# Plata1.net
KiCad netlist of a schematic drawn in EAGLE
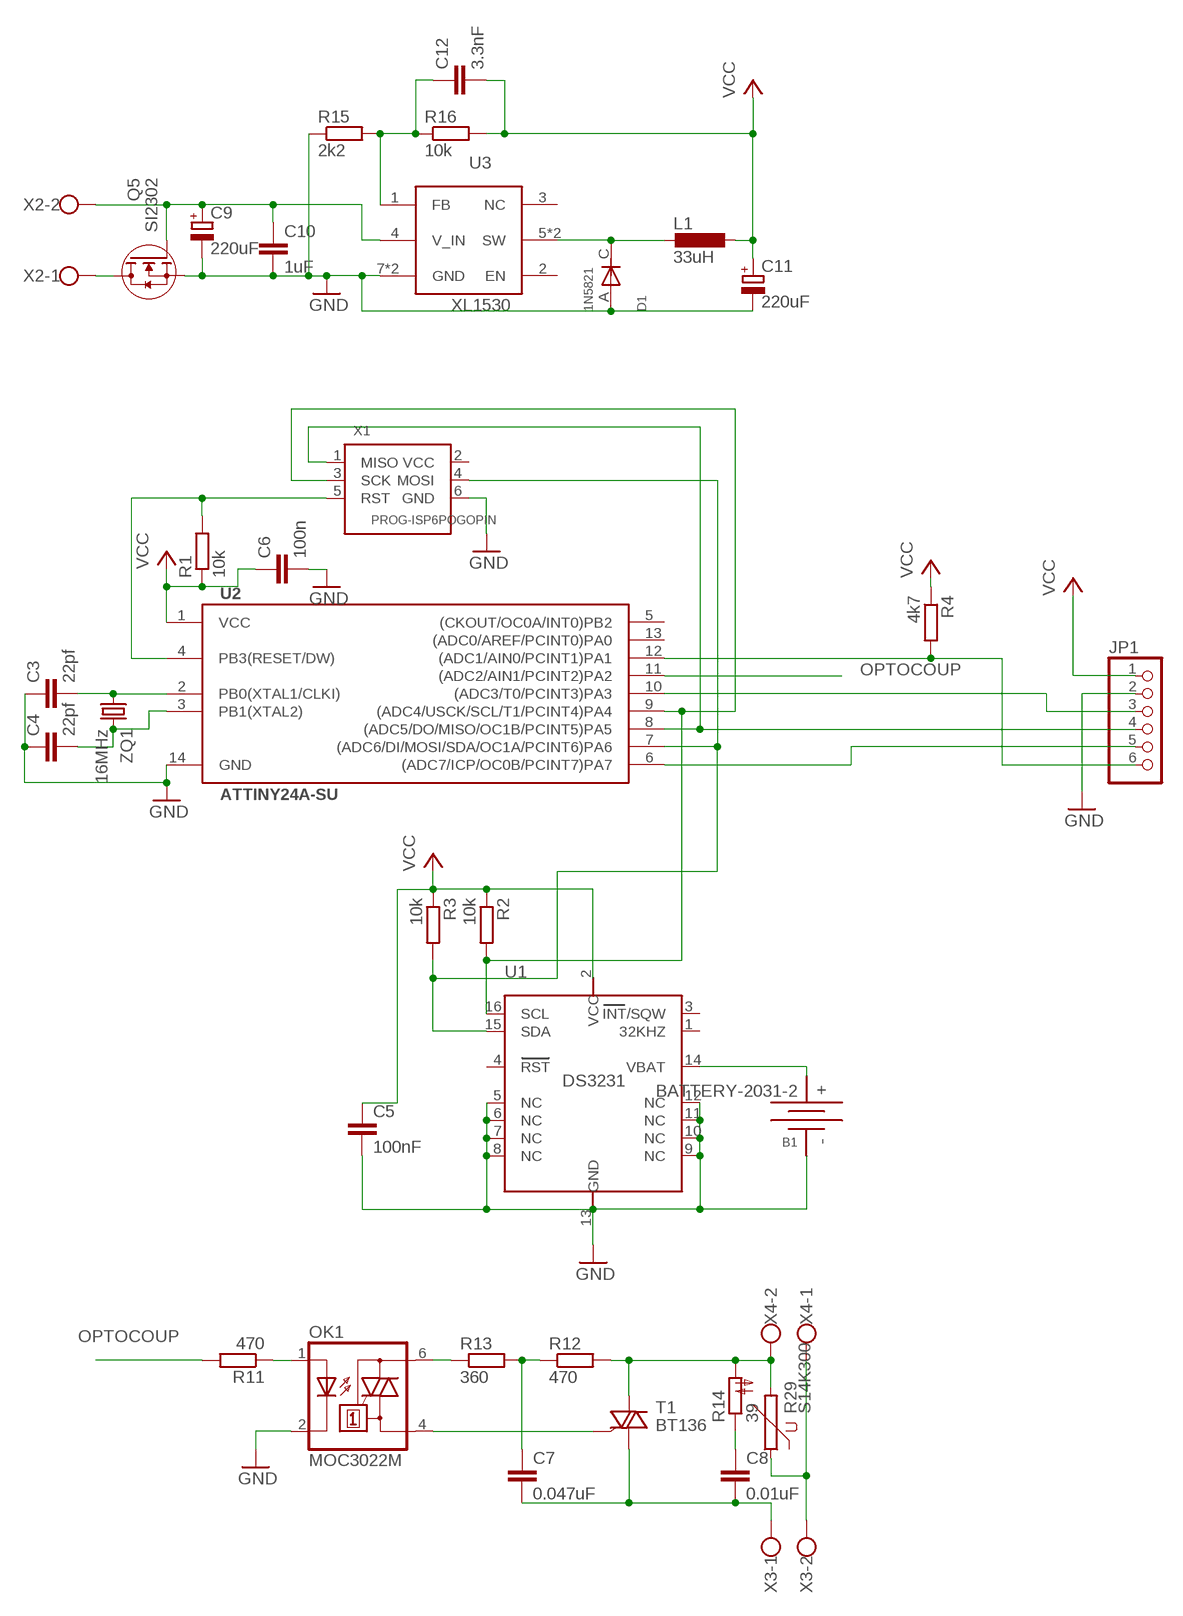
[diagram p0: schematic, sheet 1]

(export (version "E")
  (design (tool "Eeschema 10.0.6"))
  (components
    (comp (ref "B1")
      (value "BATTERY-2031-2")
      (footprint "eagle-import:BTH2032-2")
      (libsource (lib "eagle-import") (part "BATTERY-2031-2"))
    )
    (comp (ref "C3")
      (value "22pf")
      (footprint "eagle-import:C0603")
      (libsource (lib "eagle-import") (part "C-EUC0603"))
    )
    (comp (ref "C4")
      (value "22pf")
      (footprint "eagle-import:C0603")
      (libsource (lib "eagle-import") (part "C-EUC0603"))
    )
    (comp (ref "C5")
      (value "100nF")
      (footprint "eagle-import:C0603")
      (libsource (lib "eagle-import") (part "C-EUC0603"))
    )
    (comp (ref "C6")
      (value "100n")
      (footprint "eagle-import:C0603")
      (libsource (lib "eagle-import") (part "C-EUC0603"))
    )
    (comp (ref "C7")
      (value "0.047uF")
      (footprint "eagle-import:C150-054X183")
      (libsource (lib "eagle-import") (part "C-EU150-054X183"))
    )
    (comp (ref "C8")
      (value "0.01uF")
      (footprint "eagle-import:C102-043X133")
      (libsource (lib "eagle-import") (part "C-EU102-043X133"))
    )
    (comp (ref "C9")
      (value "220uF")
      (footprint "eagle-import:E2,5-6E")
      (libsource (lib "eagle-import") (part "CPOL-EUE2,5-6E"))
    )
    (comp (ref "C10")
      (value "1uF")
      (footprint "eagle-import:C0805")
      (libsource (lib "eagle-import") (part "C-EUC0805"))
    )
    (comp (ref "C11")
      (value "220uF")
      (footprint "eagle-import:E2,5-6E")
      (libsource (lib "eagle-import") (part "CPOL-EUE2,5-6E"))
    )
    (comp (ref "C12")
      (value "3.3nF")
      (footprint "eagle-import:C0805")
      (libsource (lib "eagle-import") (part "C-EUC0805"))
    )
    (comp (ref "D1")
      (value "1N5821")
      (footprint "eagle-import:DO214AC")
      (libsource (lib "eagle-import") (part "DIODESMD"))
    )
    (comp (ref "JP1")
      (value "PINHD-1X6")
      (footprint "eagle-import:1X06")
      (libsource (lib "eagle-import") (part "PINHD-1X6"))
    )
    (comp (ref "L1")
      (value "33uH")
      (footprint "eagle-import:L-SMD-D10")
      (libsource (lib "eagle-import") (part "L-SMD"))
    )
    (comp (ref "OK1")
      (value "MOC3022M")
      (footprint "eagle-import:DIL06")
      (fields (field (name "MF") "FAIRCHILD SEMICONDUCTOR") (field (name "MPN") "MOC3022-M"))
      (libsource (lib "eagle-import") (part "MOC30M22"))
    )
    (comp (ref "Q5")
      (value "SI2302")
      (footprint "eagle-import:SOT-23-GSD")
      (libsource (lib "eagle-import") (part "SI2302"))
    )
    (comp (ref "R1")
      (value "10k")
      (footprint "eagle-import:R0805")
      (libsource (lib "eagle-import") (part "R-EU_R0805"))
    )
    (comp (ref "R2")
      (value "10k")
      (footprint "eagle-import:R0805")
      (libsource (lib "eagle-import") (part "R-EU_R0805"))
    )
    (comp (ref "R3")
      (value "10k")
      (footprint "eagle-import:R0805")
      (libsource (lib "eagle-import") (part "R-EU_R0805"))
    )
    (comp (ref "R4")
      (value "4k7")
      (footprint "eagle-import:R0805")
      (libsource (lib "eagle-import") (part "R-EU_R0805"))
    )
    (comp (ref "R11")
      (value "470")
      (footprint "eagle-import:R0805")
      (libsource (lib "eagle-import") (part "R-EU_R0805"))
    )
    (comp (ref "R12")
      (value "470")
      (footprint "eagle-import:0207_7")
      (libsource (lib "eagle-import") (part "R-EU_0207/7"))
    )
    (comp (ref "R13")
      (value "360")
      (footprint "eagle-import:0207_7")
      (libsource (lib "eagle-import") (part "R-EU_0207/7"))
    )
    (comp (ref "R14")
      (value "39")
      (footprint "eagle-import:0207_7")
      (libsource (lib "eagle-import") (part "R-EU_0207/7"))
    )
    (comp (ref "R15")
      (value "2k2")
      (footprint "eagle-import:R0603")
      (libsource (lib "eagle-import") (part "R-EU_R0603"))
    )
    (comp (ref "R16")
      (value "10k")
      (footprint "eagle-import:R0603")
      (libsource (lib "eagle-import") (part "R-EU_R0603"))
    )
    (comp (ref "R29")
      (value "S14K300")
      (footprint "eagle-import:S14K300")
      (libsource (lib "eagle-import") (part "S14K300"))
    )
    (comp (ref "T1")
      (value "BT136")
      (footprint "eagle-import:TO220AB")
      (libsource (lib "eagle-import") (part "BT136"))
    )
    (comp (ref "U1")
      (value "DS3231")
      (footprint "eagle-import:SO16L")
      (libsource (lib "eagle-import") (part "DS3231"))
    )
    (comp (ref "U2")
      (value "ATTINY24A-SU")
      (footprint "eagle-import:SO14")
      (libsource (lib "eagle-import") (part "ATTINY24A-SU"))
    )
    (comp (ref "U3")
      (value "XL1530")
      (footprint "eagle-import:SOP08")
      (libsource (lib "eagle-import") (part "XL1530"))
    )
    (comp (ref "X1")
      (value "PROG-ISP6POGOPIN")
      (footprint "eagle-import:PROG_POGOPIN")
      (libsource (lib "eagle-import") (part "PROG-ISP6POGOPIN"))
    )
    (comp (ref "X2")
      (value "W237-102")
      (footprint "eagle-import:W237-102")
      (fields (field (name "MPN") "237-102"))
      (libsource (lib "eagle-import") (part "W237-102"))
    )
    (comp (ref "X3")
      (value "W237-102")
      (footprint "eagle-import:W237-102")
      (fields (field (name "MPN") "237-102"))
      (libsource (lib "eagle-import") (part "W237-102"))
    )
    (comp (ref "X4")
      (value "W237-102")
      (footprint "eagle-import:W237-102")
      (fields (field (name "MPN") "237-102"))
      (libsource (lib "eagle-import") (part "W237-102"))
    )
    (comp (ref "ZQ1")
      (value "16MHz")
      (footprint "eagle-import:HC49_S")
      (libsource (lib "eagle-import") (part "CRYSTALHC49S"))
    )
  )
  (nets
    (net (code "1") (name "/OPTOCOUP") (class "Default")
      (node (ref "R11") (pin "2") (pinfunction "2_2") (pintype "passive"))
      (node (ref "U2") (pin "11") (pinfunction "(ADC2/AIN1/PCINT2)PA2_11") (pintype "bidirectional"))
    )
    (net (code "2") (name "GND") (class "Default")
      (node (ref "B1") (pin "-") (pinfunction "-_-") (pintype "power_in"))
      (node (ref "C10") (pin "2") (pinfunction "2_2") (pintype "passive"))
      (node (ref "C11") (pin "-") (pinfunction "-_-") (pintype "passive"))
      (node (ref "C3") (pin "1") (pinfunction "1_1") (pintype "passive"))
      (node (ref "C4") (pin "1") (pinfunction "1_1") (pintype "passive"))
      (node (ref "C5") (pin "2") (pinfunction "2_2") (pintype "passive"))
      (node (ref "C6") (pin "2") (pinfunction "2_2") (pintype "passive"))
      (node (ref "C9") (pin "-") (pinfunction "-_-") (pintype "passive"))
      (node (ref "D1") (pin "A") (pinfunction "ANOD_A") (pintype "power_in"))
      (node (ref "JP1") (pin "2") (pinfunction "2_2") (pintype "passive"))
      (node (ref "OK1") (pin "2") (pinfunction "C_2") (pintype "passive"))
      (node (ref "Q5") (pin "S") (pinfunction "S_S") (pintype "passive"))
      (node (ref "R15") (pin "1") (pinfunction "1_1") (pintype "passive"))
      (node (ref "U1") (pin "10") (pinfunction "NC_10") (pintype "bidirectional"))
      (node (ref "U1") (pin "11") (pinfunction "NC_11") (pintype "bidirectional"))
      (node (ref "U1") (pin "12") (pinfunction "NC_12") (pintype "bidirectional"))
      (node (ref "U1") (pin "13") (pinfunction "GND_13") (pintype "power_in"))
      (node (ref "U1") (pin "5") (pinfunction "NC_5") (pintype "bidirectional"))
      (node (ref "U1") (pin "6") (pinfunction "NC_6") (pintype "bidirectional"))
      (node (ref "U1") (pin "7") (pinfunction "NC_7") (pintype "bidirectional"))
      (node (ref "U1") (pin "8") (pinfunction "NC_8") (pintype "bidirectional"))
      (node (ref "U1") (pin "9") (pinfunction "NC_9") (pintype "bidirectional"))
      (node (ref "U2") (pin "14") (pinfunction "GND_14") (pintype "power_in"))
      (node (ref "U3") (pin "7") (pinfunction "GND_7") (pintype "bidirectional"))
      (node (ref "U3") (pin "8") (pinfunction "GND_8") (pintype "bidirectional"))
      (node (ref "X1") (pin "6") (pinfunction "GND_6") (pintype "power_in"))
    )
    (net (code "3") (name "Net-(C7-Pad1)") (class "Default")
      (node (ref "C7") (pin "1") (pinfunction "1_1") (pintype "passive"))
      (node (ref "R12") (pin "1") (pinfunction "1_1") (pintype "passive"))
      (node (ref "R13") (pin "2") (pinfunction "2_2") (pintype "passive"))
    )
    (net (code "4") (name "Net-(C8-Pad1)") (class "Default")
      (node (ref "C8") (pin "1") (pinfunction "1_1") (pintype "passive"))
      (node (ref "R14") (pin "1") (pinfunction "1_1") (pintype "passive"))
    )
    (net (code "5") (name "Net-(D1-KATOD)") (class "Default")
      (node (ref "D1") (pin "C") (pinfunction "KATOD_C") (pintype "power_in"))
      (node (ref "L1") (pin "P$2") (pinfunction "2_P$2") (pintype "passive"))
      (node (ref "U3") (pin "5") (pinfunction "SW_5") (pintype "bidirectional"))
      (node (ref "U3") (pin "6") (pinfunction "SW_6") (pintype "bidirectional"))
    )
    (net (code "6") (name "Net-(OK1-A)") (class "Default")
      (node (ref "OK1") (pin "1") (pinfunction "A_1") (pintype "passive"))
      (node (ref "R11") (pin "1") (pinfunction "1_1") (pintype "passive"))
    )
    (net (code "7") (name "Net-(OK1-A1)") (class "Default")
      (node (ref "OK1") (pin "4") (pinfunction "A1_4") (pintype "passive"))
      (node (ref "T1") (pin "3") (pinfunction "G_3") (pintype "passive"))
    )
    (net (code "8") (name "Net-(OK1-A2)") (class "Default")
      (node (ref "OK1") (pin "6") (pinfunction "A2_6") (pintype "passive"))
      (node (ref "R13") (pin "1") (pinfunction "1_1") (pintype "passive"))
    )
    (net (code "9") (name "Net-(T1-A1)") (class "Default")
      (node (ref "C7") (pin "2") (pinfunction "2_2") (pintype "passive"))
      (node (ref "C8") (pin "2") (pinfunction "2_2") (pintype "passive"))
      (node (ref "T1") (pin "1") (pinfunction "A1_1") (pintype "passive"))
      (node (ref "X3") (pin "1") (pinfunction "KL_1") (pintype "passive"))
    )
    (net (code "10") (name "Net-(T1-A2)") (class "Default")
      (node (ref "R12") (pin "2") (pinfunction "2_2") (pintype "passive"))
      (node (ref "R14") (pin "2") (pinfunction "2_2") (pintype "passive"))
      (node (ref "R29") (pin "2") (pinfunction "2_2") (pintype "passive"))
      (node (ref "T1") (pin "2") (pinfunction "A2_2") (pintype "passive"))
      (node (ref "X4") (pin "2") (pinfunction "KL_2") (pintype "passive"))
    )
    (net (code "11") (name "Net-(U1-SCL)") (class "Default")
      (node (ref "R2") (pin "2") (pinfunction "2_2") (pintype "passive"))
      (node (ref "U1") (pin "16") (pinfunction "SCL_16") (pintype "bidirectional"))
      (node (ref "U2") (pin "9") (pinfunction "(ADC4/USCK/SCL/T1/PCINT4)PA4_9") (pintype "bidirectional"))
      (node (ref "X1") (pin "3") (pinfunction "SCK_3") (pintype "bidirectional"))
    )
    (net (code "12") (name "Net-(U1-SDA)") (class "Default")
      (node (ref "R3") (pin "2") (pinfunction "2_2") (pintype "passive"))
      (node (ref "U1") (pin "15") (pinfunction "SDA_15") (pintype "bidirectional"))
      (node (ref "U2") (pin "7") (pinfunction "(ADC6/DI/MOSI/SDA/OC1A/PCINT6)PA6_7") (pintype "bidirectional"))
      (node (ref "X1") (pin "4") (pinfunction "MOSI_4") (pintype "bidirectional"))
    )
    (net (code "13") (name "Net-(U1-VBAT)") (class "Default")
      (node (ref "B1") (pin "+") (pinfunction "+_+") (pintype "power_in"))
      (node (ref "U1") (pin "14") (pinfunction "VBAT_14") (pintype "bidirectional"))
    )
    (net (code "14") (name "Net-(U2-(ADC1{slash}AIN0{slash}PCINT1)PA1)") (class "Default")
      (node (ref "JP1") (pin "6") (pinfunction "6_6") (pintype "passive"))
      (node (ref "R4") (pin "2") (pinfunction "2_2") (pintype "passive"))
      (node (ref "U2") (pin "12") (pinfunction "(ADC1/AIN0/PCINT1)PA1_12") (pintype "bidirectional"))
    )
    (net (code "15") (name "Net-(U2-(ADC3{slash}T0{slash}PCINT3)PA3)") (class "Default")
      (node (ref "JP1") (pin "3") (pinfunction "3_3") (pintype "passive"))
      (node (ref "U2") (pin "10") (pinfunction "(ADC3/T0/PCINT3)PA3_10") (pintype "bidirectional"))
    )
    (net (code "16") (name "Net-(U2-(ADC5{slash}DO{slash}MISO{slash}OC1B{slash}PCINT5)PA5)") (class "Default")
      (node (ref "JP1") (pin "4") (pinfunction "4_4") (pintype "passive"))
      (node (ref "U2") (pin "8") (pinfunction "(ADC5/DO/MISO/OC1B/PCINT5)PA5_8") (pintype "bidirectional"))
      (node (ref "X1") (pin "1") (pinfunction "MISO_1") (pintype "bidirectional"))
    )
    (net (code "17") (name "Net-(U2-(ADC7{slash}ICP{slash}OC0B{slash}PCINT7)PA7)") (class "Default")
      (node (ref "JP1") (pin "5") (pinfunction "5_5") (pintype "passive"))
      (node (ref "U2") (pin "6") (pinfunction "(ADC7/ICP/OC0B/PCINT7)PA7_6") (pintype "bidirectional"))
    )
    (net (code "18") (name "Net-(U2-PB0(XTAL1{slash}CLKI))") (class "Default")
      (node (ref "C3") (pin "2") (pinfunction "2_2") (pintype "passive"))
      (node (ref "U2") (pin "2") (pinfunction "PB0(XTAL1/CLKI)_2") (pintype "bidirectional"))
      (node (ref "ZQ1") (pin "1") (pinfunction "1_1") (pintype "passive"))
    )
    (net (code "19") (name "Net-(U2-PB1(XTAL2))") (class "Default")
      (node (ref "C4") (pin "2") (pinfunction "2_2") (pintype "passive"))
      (node (ref "U2") (pin "3") (pinfunction "PB1(XTAL2)_3") (pintype "bidirectional"))
      (node (ref "ZQ1") (pin "2") (pinfunction "2_2") (pintype "passive"))
    )
    (net (code "20") (name "Net-(U2-PB3(RESET{slash}DW))") (class "Default")
      (node (ref "R1") (pin "2") (pinfunction "2_2") (pintype "passive"))
      (node (ref "U2") (pin "4") (pinfunction "PB3(RESET/DW)_4") (pintype "bidirectional"))
      (node (ref "X1") (pin "5") (pinfunction "RST_5") (pintype "bidirectional"))
    )
    (net (code "21") (name "Net-(U3-FB)") (class "Default")
      (node (ref "C12") (pin "1") (pinfunction "1_1") (pintype "passive"))
      (node (ref "R15") (pin "2") (pinfunction "2_2") (pintype "passive"))
      (node (ref "R16") (pin "1") (pinfunction "1_1") (pintype "passive"))
      (node (ref "U3") (pin "1") (pinfunction "FB_1") (pintype "bidirectional"))
    )
    (net (code "22") (name "Net-(U3-V_IN)") (class "Default")
      (node (ref "C10") (pin "1") (pinfunction "1_1") (pintype "passive"))
      (node (ref "C9") (pin "+") (pinfunction "+_+") (pintype "passive"))
      (node (ref "Q5") (pin "G") (pinfunction "G_G") (pintype "passive"))
      (node (ref "U3") (pin "4") (pinfunction "V_IN_4") (pintype "bidirectional"))
      (node (ref "X2") (pin "2") (pinfunction "KL_2") (pintype "passive"))
    )
    (net (code "23") (name "Net-(X2A-KL)") (class "Default")
      (node (ref "Q5") (pin "D") (pinfunction "D_D") (pintype "passive"))
      (node (ref "X2") (pin "1") (pinfunction "KL_1") (pintype "passive"))
    )
    (net (code "24") (name "Net-(X3B-KL)") (class "Default")
      (node (ref "R29") (pin "1") (pinfunction "1_1") (pintype "passive"))
      (node (ref "X3") (pin "2") (pinfunction "KL_2") (pintype "passive"))
      (node (ref "X4") (pin "1") (pinfunction "KL_1") (pintype "passive"))
    )
    (net (code "25") (name "VCC") (class "Default")
      (node (ref "C11") (pin "+") (pinfunction "+_+") (pintype "passive"))
      (node (ref "C12") (pin "2") (pinfunction "2_2") (pintype "passive"))
      (node (ref "C5") (pin "1") (pinfunction "1_1") (pintype "passive"))
      (node (ref "C6") (pin "1") (pinfunction "1_1") (pintype "passive"))
      (node (ref "JP1") (pin "1") (pinfunction "1_1") (pintype "passive"))
      (node (ref "L1") (pin "P$1") (pinfunction "1_P$1") (pintype "passive"))
      (node (ref "R1") (pin "1") (pinfunction "1_1") (pintype "passive"))
      (node (ref "R16") (pin "2") (pinfunction "2_2") (pintype "passive"))
      (node (ref "R2") (pin "1") (pinfunction "1_1") (pintype "passive"))
      (node (ref "R3") (pin "1") (pinfunction "1_1") (pintype "passive"))
      (node (ref "R4") (pin "1") (pinfunction "1_1") (pintype "passive"))
      (node (ref "U1") (pin "2") (pinfunction "VCC_2") (pintype "power_in"))
      (node (ref "U2") (pin "1") (pinfunction "VCC_1") (pintype "power_in"))
    )
    (net (code "26") (name "unconnected-(U1-32KHZ-Pad1)") (class "Default")
      (node (ref "U1") (pin "1") (pinfunction "32KHZ_1") (pintype "bidirectional"))
    )
    (net (code "27") (name "unconnected-(U1-INT{slash}SQW-Pad3)") (class "Default")
      (node (ref "U1") (pin "3") (pinfunction "INT/SQW_3") (pintype "bidirectional"))
    )
    (net (code "28") (name "unconnected-(U1-RST-Pad4)") (class "Default")
      (node (ref "U1") (pin "4") (pinfunction "RST_4") (pintype "bidirectional"))
    )
    (net (code "29") (name "unconnected-(U2-(ADC0{slash}AREF{slash}PCINT0)PA0-Pad13)") (class "Default")
      (node (ref "U2") (pin "13") (pinfunction "(ADC0/AREF/PCINT0)PA0_13") (pintype "bidirectional"))
    )
    (net (code "30") (name "unconnected-(U2-(CKOUT{slash}OC0A{slash}INT0)PB2-Pad5)") (class "Default")
      (node (ref "U2") (pin "5") (pinfunction "(CKOUT/OC0A/INT0)PB2_5") (pintype "bidirectional"))
    )
    (net (code "31") (name "unconnected-(U3-EN-Pad2)") (class "Default")
      (node (ref "U3") (pin "2") (pinfunction "EN_2") (pintype "bidirectional"))
    )
    (net (code "32") (name "unconnected-(U3-NC-Pad3)") (class "Default")
      (node (ref "U3") (pin "3") (pinfunction "NC_3") (pintype "bidirectional"))
    )
    (net (code "33") (name "unconnected-(X1-VCC-Pad2)") (class "Default")
      (node (ref "X1") (pin "2") (pinfunction "VCC_2") (pintype "bidirectional"))
    )
  )
)
